# siguelineas.net
KiCad netlist of a schematic drawn in EAGLE
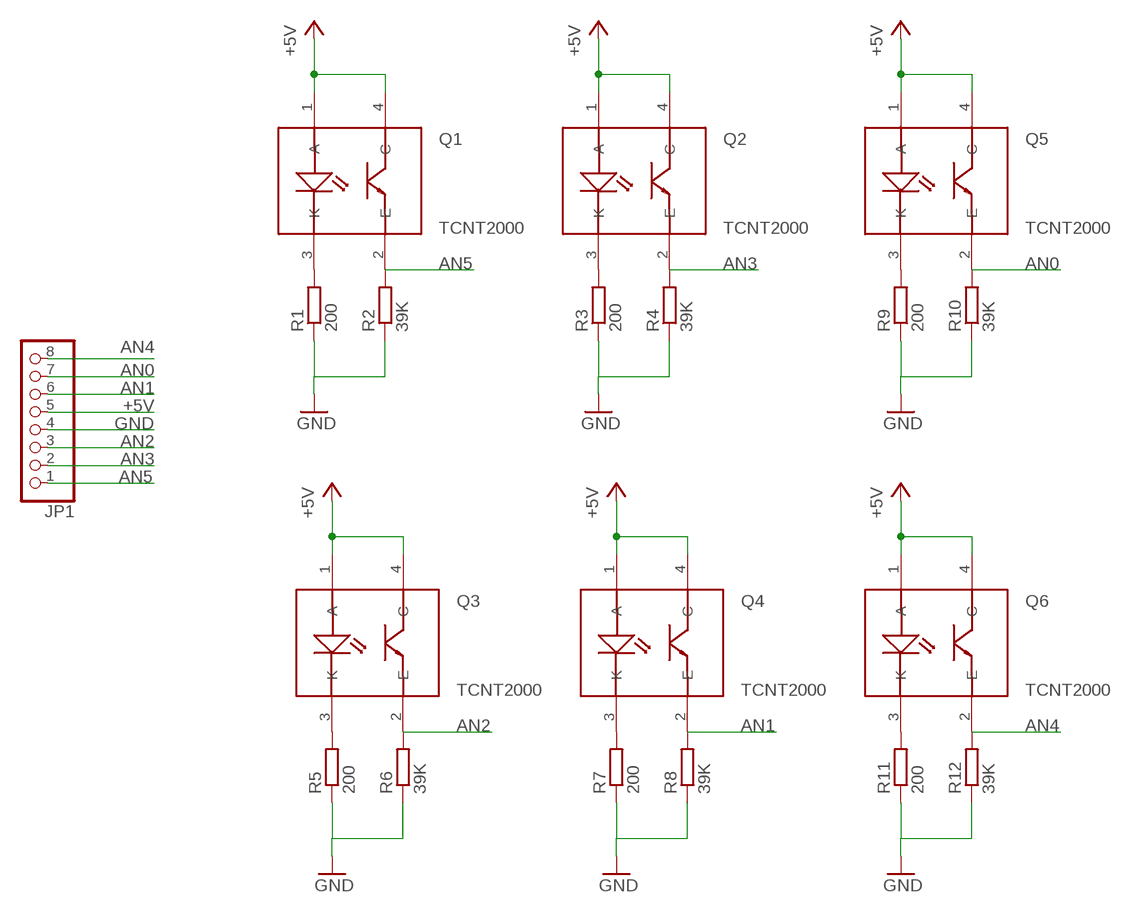
[diagram p0: schematic, sheet 1]

(export (version "E")
  (design (tool "Eeschema 10.0.6"))
  (components
    (comp (ref "JP1")
      (value "PINHD-1X8")
      (footprint "eagle-import:1X08")
      (libsource (lib "eagle-import") (part "PINHD-1X8"))
    )
    (comp (ref "Q1")
      (value "TCNT2000")
      (footprint "eagle-import:SMD")
      (libsource (lib "eagle-import") (part "TCNT2000"))
    )
    (comp (ref "Q2")
      (value "TCNT2000")
      (footprint "eagle-import:SMD")
      (libsource (lib "eagle-import") (part "TCNT2000"))
    )
    (comp (ref "Q3")
      (value "TCNT2000")
      (footprint "eagle-import:SMD")
      (libsource (lib "eagle-import") (part "TCNT2000"))
    )
    (comp (ref "Q4")
      (value "TCNT2000")
      (footprint "eagle-import:SMD")
      (libsource (lib "eagle-import") (part "TCNT2000"))
    )
    (comp (ref "Q5")
      (value "TCNT2000")
      (footprint "eagle-import:SMD")
      (libsource (lib "eagle-import") (part "TCNT2000"))
    )
    (comp (ref "Q6")
      (value "TCNT2000")
      (footprint "eagle-import:SMD")
      (libsource (lib "eagle-import") (part "TCNT2000"))
    )
    (comp (ref "R1")
      (value "200")
      (footprint "eagle-import:R0805")
      (libsource (lib "eagle-import") (part "R-EU_R0805"))
    )
    (comp (ref "R2")
      (value "39K")
      (footprint "eagle-import:R0805")
      (libsource (lib "eagle-import") (part "R-EU_R0805"))
    )
    (comp (ref "R3")
      (value "200")
      (footprint "eagle-import:R0805")
      (libsource (lib "eagle-import") (part "R-EU_R0805"))
    )
    (comp (ref "R4")
      (value "39K")
      (footprint "eagle-import:R0805")
      (libsource (lib "eagle-import") (part "R-EU_R0805"))
    )
    (comp (ref "R5")
      (value "200")
      (footprint "eagle-import:R0805")
      (libsource (lib "eagle-import") (part "R-EU_R0805"))
    )
    (comp (ref "R6")
      (value "39K")
      (footprint "eagle-import:R0805")
      (libsource (lib "eagle-import") (part "R-EU_R0805"))
    )
    (comp (ref "R7")
      (value "200")
      (footprint "eagle-import:R0805")
      (libsource (lib "eagle-import") (part "R-EU_R0805"))
    )
    (comp (ref "R8")
      (value "39K")
      (footprint "eagle-import:R0805")
      (libsource (lib "eagle-import") (part "R-EU_R0805"))
    )
    (comp (ref "R9")
      (value "200")
      (footprint "eagle-import:R0805")
      (libsource (lib "eagle-import") (part "R-EU_R0805"))
    )
    (comp (ref "R10")
      (value "39K")
      (footprint "eagle-import:R0805")
      (libsource (lib "eagle-import") (part "R-EU_R0805"))
    )
    (comp (ref "R11")
      (value "200")
      (footprint "eagle-import:R0805")
      (libsource (lib "eagle-import") (part "R-EU_R0805"))
    )
    (comp (ref "R12")
      (value "39K")
      (footprint "eagle-import:R0805")
      (libsource (lib "eagle-import") (part "R-EU_R0805"))
    )
  )
  (nets
    (net (code "1") (name "+5V") (class "Default")
      (node (ref "JP1") (pin "5") (pinfunction "5_5") (pintype "passive"))
      (node (ref "Q1") (pin "1") (pinfunction "A_1") (pintype "bidirectional"))
      (node (ref "Q1") (pin "4") (pinfunction "C_4") (pintype "bidirectional"))
      (node (ref "Q2") (pin "1") (pinfunction "A_1") (pintype "bidirectional"))
      (node (ref "Q2") (pin "4") (pinfunction "C_4") (pintype "bidirectional"))
      (node (ref "Q3") (pin "1") (pinfunction "A_1") (pintype "bidirectional"))
      (node (ref "Q3") (pin "4") (pinfunction "C_4") (pintype "bidirectional"))
      (node (ref "Q4") (pin "1") (pinfunction "A_1") (pintype "bidirectional"))
      (node (ref "Q4") (pin "4") (pinfunction "C_4") (pintype "bidirectional"))
      (node (ref "Q5") (pin "1") (pinfunction "A_1") (pintype "bidirectional"))
      (node (ref "Q5") (pin "4") (pinfunction "C_4") (pintype "bidirectional"))
      (node (ref "Q6") (pin "1") (pinfunction "A_1") (pintype "bidirectional"))
      (node (ref "Q6") (pin "4") (pinfunction "C_4") (pintype "bidirectional"))
    )
    (net (code "2") (name "/AN0") (class "Default")
      (node (ref "JP1") (pin "7") (pinfunction "7_7") (pintype "passive"))
      (node (ref "Q5") (pin "2") (pinfunction "E_2") (pintype "bidirectional"))
      (node (ref "R10") (pin "2") (pinfunction "2_2") (pintype "passive"))
    )
    (net (code "3") (name "/AN1") (class "Default")
      (node (ref "JP1") (pin "6") (pinfunction "6_6") (pintype "passive"))
      (node (ref "Q4") (pin "2") (pinfunction "E_2") (pintype "bidirectional"))
      (node (ref "R8") (pin "2") (pinfunction "2_2") (pintype "passive"))
    )
    (net (code "4") (name "/AN2") (class "Default")
      (node (ref "JP1") (pin "3") (pinfunction "3_3") (pintype "passive"))
      (node (ref "Q3") (pin "2") (pinfunction "E_2") (pintype "bidirectional"))
      (node (ref "R6") (pin "2") (pinfunction "2_2") (pintype "passive"))
    )
    (net (code "5") (name "/AN3") (class "Default")
      (node (ref "JP1") (pin "2") (pinfunction "2_2") (pintype "passive"))
      (node (ref "Q2") (pin "2") (pinfunction "E_2") (pintype "bidirectional"))
      (node (ref "R4") (pin "2") (pinfunction "2_2") (pintype "passive"))
    )
    (net (code "6") (name "/AN4") (class "Default")
      (node (ref "JP1") (pin "8") (pinfunction "8_8") (pintype "passive"))
      (node (ref "Q6") (pin "2") (pinfunction "E_2") (pintype "bidirectional"))
      (node (ref "R12") (pin "2") (pinfunction "2_2") (pintype "passive"))
    )
    (net (code "7") (name "/AN5") (class "Default")
      (node (ref "JP1") (pin "1") (pinfunction "1_1") (pintype "passive"))
      (node (ref "Q1") (pin "2") (pinfunction "E_2") (pintype "bidirectional"))
      (node (ref "R2") (pin "2") (pinfunction "2_2") (pintype "passive"))
    )
    (net (code "8") (name "GND") (class "Default")
      (node (ref "JP1") (pin "4") (pinfunction "4_4") (pintype "passive"))
      (node (ref "R1") (pin "1") (pinfunction "1_1") (pintype "passive"))
      (node (ref "R10") (pin "1") (pinfunction "1_1") (pintype "passive"))
      (node (ref "R11") (pin "1") (pinfunction "1_1") (pintype "passive"))
      (node (ref "R12") (pin "1") (pinfunction "1_1") (pintype "passive"))
      (node (ref "R2") (pin "1") (pinfunction "1_1") (pintype "passive"))
      (node (ref "R3") (pin "1") (pinfunction "1_1") (pintype "passive"))
      (node (ref "R4") (pin "1") (pinfunction "1_1") (pintype "passive"))
      (node (ref "R5") (pin "1") (pinfunction "1_1") (pintype "passive"))
      (node (ref "R6") (pin "1") (pinfunction "1_1") (pintype "passive"))
      (node (ref "R7") (pin "1") (pinfunction "1_1") (pintype "passive"))
      (node (ref "R8") (pin "1") (pinfunction "1_1") (pintype "passive"))
      (node (ref "R9") (pin "1") (pinfunction "1_1") (pintype "passive"))
    )
    (net (code "9") (name "Net-(Q1-K)") (class "Default")
      (node (ref "Q1") (pin "3") (pinfunction "K_3") (pintype "bidirectional"))
      (node (ref "R1") (pin "2") (pinfunction "2_2") (pintype "passive"))
    )
    (net (code "10") (name "Net-(Q2-K)") (class "Default")
      (node (ref "Q2") (pin "3") (pinfunction "K_3") (pintype "bidirectional"))
      (node (ref "R3") (pin "2") (pinfunction "2_2") (pintype "passive"))
    )
    (net (code "11") (name "Net-(Q3-K)") (class "Default")
      (node (ref "Q3") (pin "3") (pinfunction "K_3") (pintype "bidirectional"))
      (node (ref "R5") (pin "2") (pinfunction "2_2") (pintype "passive"))
    )
    (net (code "12") (name "Net-(Q4-K)") (class "Default")
      (node (ref "Q4") (pin "3") (pinfunction "K_3") (pintype "bidirectional"))
      (node (ref "R7") (pin "2") (pinfunction "2_2") (pintype "passive"))
    )
    (net (code "13") (name "Net-(Q5-K)") (class "Default")
      (node (ref "Q5") (pin "3") (pinfunction "K_3") (pintype "bidirectional"))
      (node (ref "R9") (pin "2") (pinfunction "2_2") (pintype "passive"))
    )
    (net (code "14") (name "Net-(Q6-K)") (class "Default")
      (node (ref "Q6") (pin "3") (pinfunction "K_3") (pintype "bidirectional"))
      (node (ref "R11") (pin "2") (pinfunction "2_2") (pintype "passive"))
    )
  )
)
